# SolarTracker.net
KiCad netlist of a schematic drawn in EAGLE
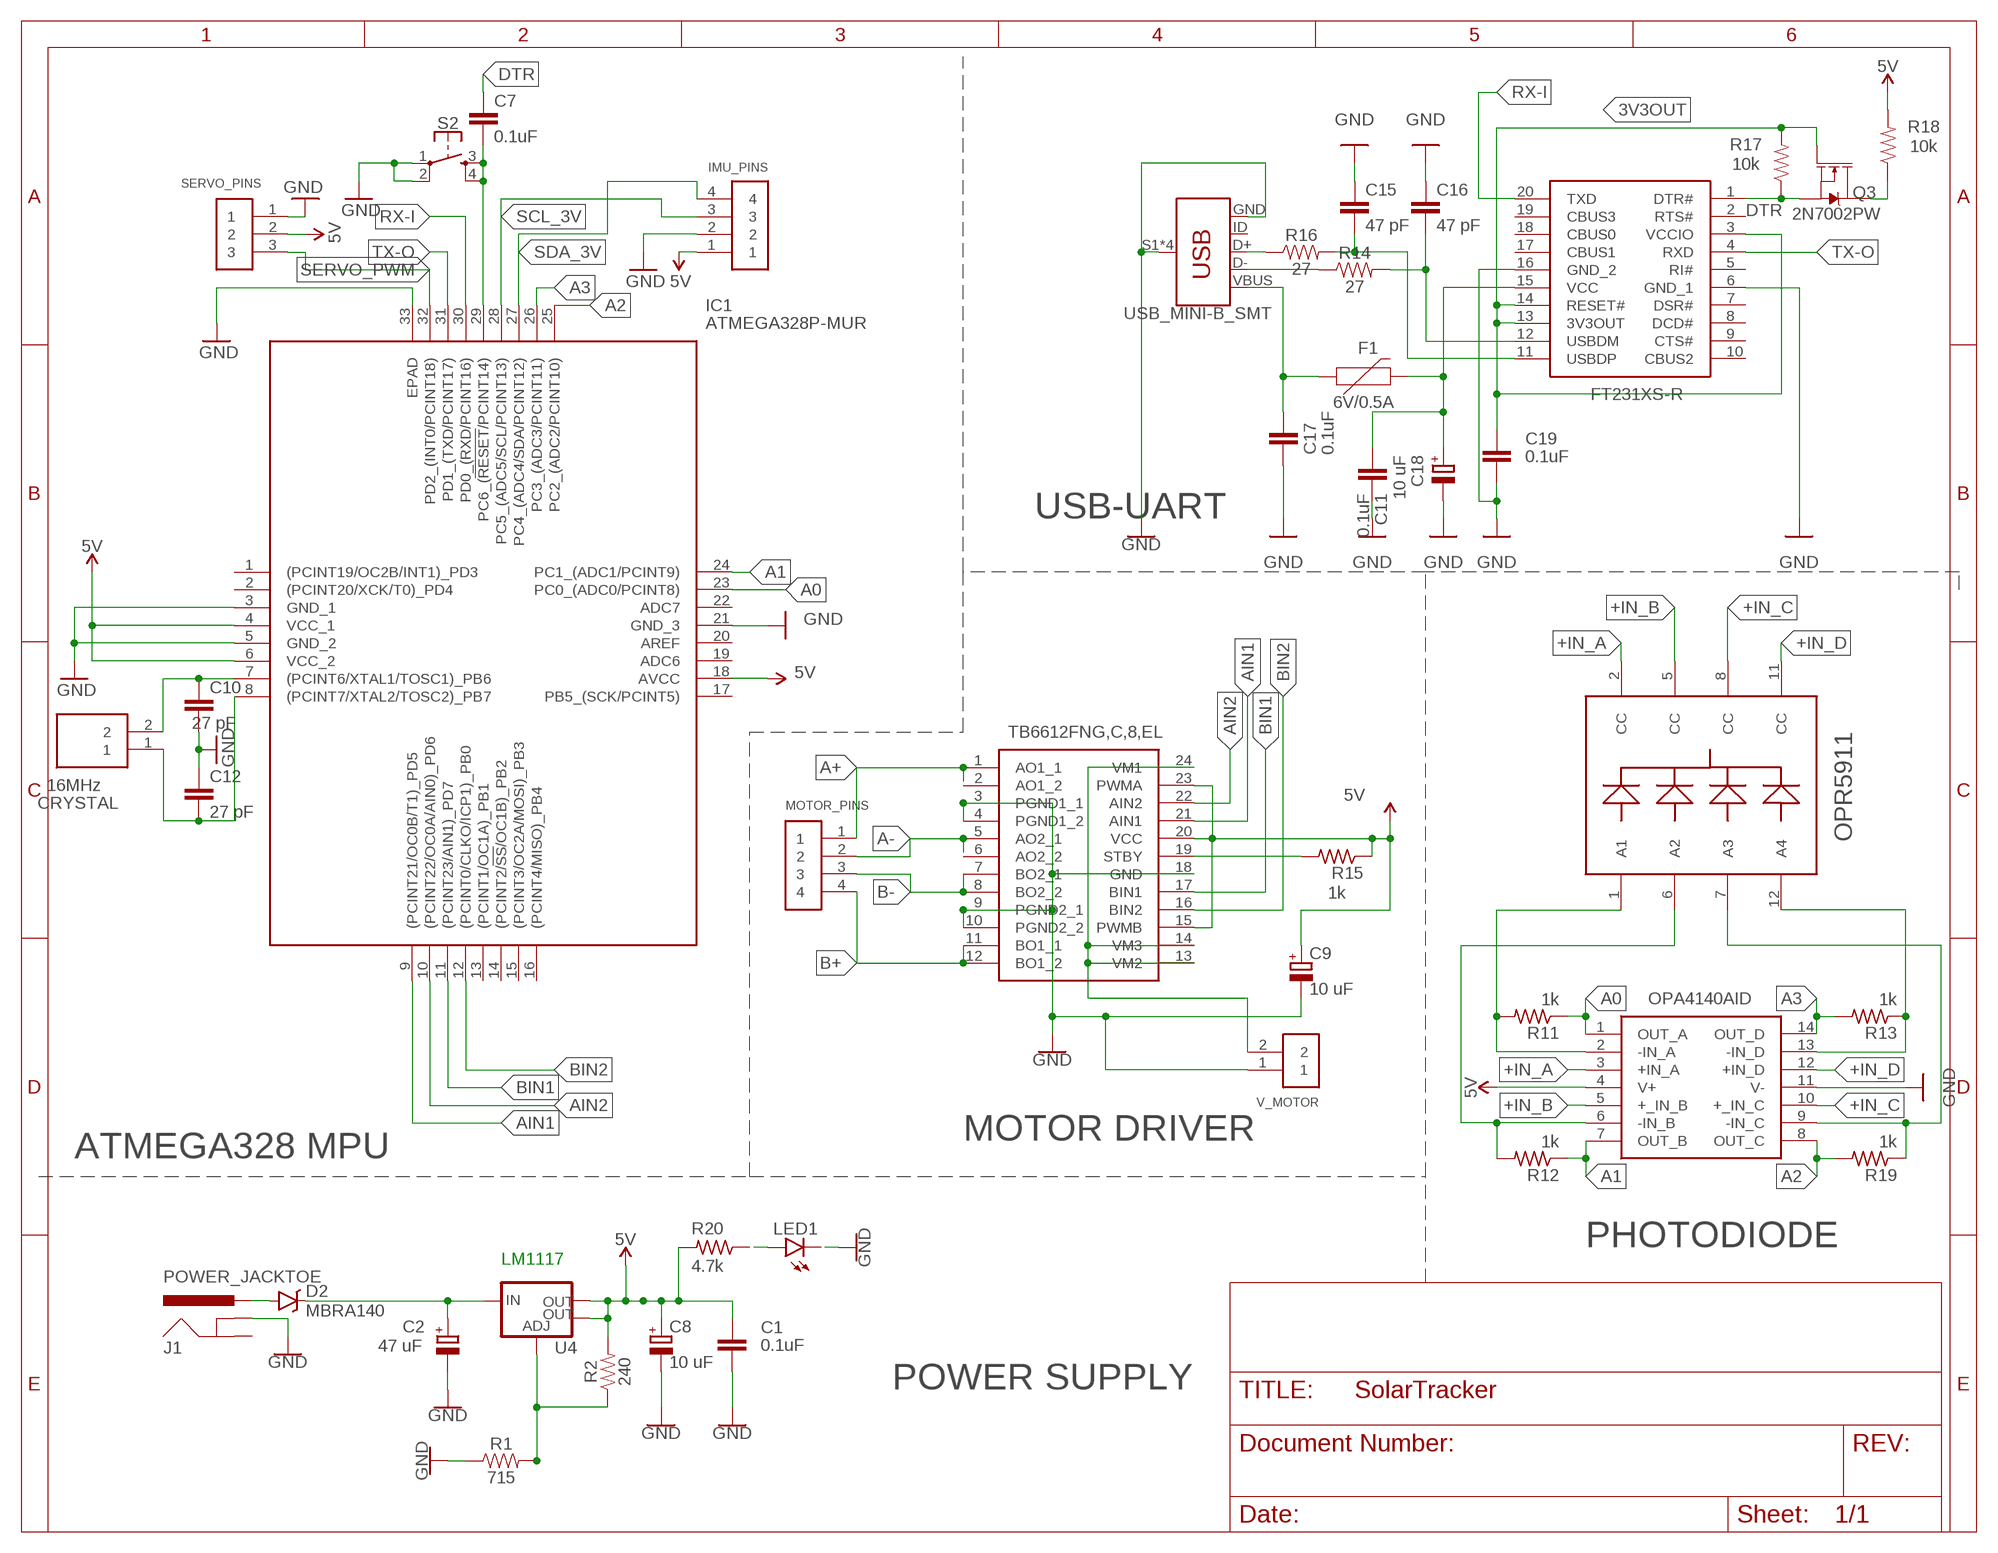
[diagram p0: schematic, sheet 1]

(export (version "E")
  (design (tool "Eeschema 10.0.6"))
  (components
    (comp (ref "C1")
      (value "0.1uF")
      (footprint "eagle-import:C0603")
      (libsource (lib "eagle-import") (part "C-EUC0603"))
    )
    (comp (ref "C2")
      (value "47 uF")
      (footprint "eagle-import:E2,5-6")
      (libsource (lib "eagle-import") (part "CPOL-EUE2.5-6"))
    )
    (comp (ref "C7")
      (value "0.1uF")
      (footprint "eagle-import:C0603")
      (libsource (lib "eagle-import") (part "C-EUC0603"))
    )
    (comp (ref "C8")
      (value "10 uF")
      (footprint "eagle-import:E2,5-6")
      (libsource (lib "eagle-import") (part "CPOL-EUE2.5-6"))
    )
    (comp (ref "C9")
      (value "10 uF")
      (footprint "eagle-import:E2,5-6")
      (libsource (lib "eagle-import") (part "CPOL-EUE2.5-6"))
    )
    (comp (ref "C10")
      (value "27 pF")
      (footprint "eagle-import:C025-025X050")
      (libsource (lib "eagle-import") (part "C-EU025-025X050"))
    )
    (comp (ref "C11")
      (value "0.1uF")
      (footprint "eagle-import:C0603")
      (libsource (lib "eagle-import") (part "C-EUC0603"))
    )
    (comp (ref "C12")
      (value "27 pF")
      (footprint "eagle-import:C025-025X050")
      (libsource (lib "eagle-import") (part "C-EU025-025X050"))
    )
    (comp (ref "C15")
      (value "47 pF")
      (footprint "eagle-import:C0805")
      (libsource (lib "eagle-import") (part "C-EUC0805"))
    )
    (comp (ref "C16")
      (value "47 pF")
      (footprint "eagle-import:C0805")
      (libsource (lib "eagle-import") (part "C-EUC0805"))
    )
    (comp (ref "C17")
      (value "0.1uF")
      (footprint "eagle-import:C0603")
      (libsource (lib "eagle-import") (part "C-EUC0603"))
    )
    (comp (ref "C18")
      (value "10 uF")
      (footprint "eagle-import:E2,5-6")
      (libsource (lib "eagle-import") (part "CPOL-EUE2.5-6"))
    )
    (comp (ref "C19")
      (value "0.1uF")
      (footprint "eagle-import:C0603")
      (libsource (lib "eagle-import") (part "C-EUC0603"))
    )
    (comp (ref "CRYSTAL")
      (value "16MHz")
      (footprint "eagle-import:HC49")
      (fields
        (field (name "MANUFACTURER_PART_NUMBER") "HC-49/U-S16000000ABJB")
        (field (name "MOUSER_PART_NUMBER") "695-HC49US16.0ABJB")
      )
      (libsource (lib "eagle-import") (part "HC-49_U-S16000000ABJB"))
    )
    (comp (ref "D2")
      (value "MBRA140")
      (footprint "eagle-import:SMA-DIODE")
      (fields (field (name "MF") "ON Semiconductor"))
      (libsource (lib "eagle-import") (part "MBRA140"))
    )
    (comp (ref "F1")
      (value "6V/0.5A")
      (footprint "eagle-import:1206")
      (libsource (lib "eagle-import") (part "PTC-HALF_AMP"))
    )
    (comp (ref "IC1")
      (value "ATMEGA328P-MUR")
      (footprint "eagle-import:QFN50P500X500X100-33N")
      (fields (field (name "MOUSER_PART_NUMBER") "556-ATMEGA328P-MUR"))
      (libsource (lib "eagle-import") (part "ATMEGA328P-MUR"))
    )
    (comp (ref "IC2")
      (value "FT231XS-R")
      (footprint "eagle-import:SOP64P599X175-20N")
      (libsource (lib "eagle-import") (part "FT231XS-R"))
    )
    (comp (ref "IC3")
      (value "OPA4140AID")
      (footprint "eagle-import:SOIC127P600X175-14N")
      (fields (field (name "MOUSER_PART_NUMBER") "595-OPA4140AID"))
      (libsource (lib "eagle-import") (part "OPA4140AID"))
    )
    (comp (ref "J1")
      (value "POWER_JACKTOE")
      (footprint "eagle-import:POWER_JACK_SMD_OVERPASTE_TOE")
      (libsource (lib "eagle-import") (part "POWER_JACKTOE"))
    )
    (comp (ref "J2")
      (value "USB_MINI-B_SMT")
      (footprint "eagle-import:USB-MINIB")
      (libsource (lib "eagle-import") (part "USB_MINI-B_SMT"))
    )
    (comp (ref "J4")
      (value "IMU_PINS")
      (footprint "eagle-import:61300411121")
      (fields
        (field (name "DIGI_KEY_PART_NUMBER") "732-5317-ND")
        (field (name "MANUFACTURER") "Wurth Electronics Inc.")
        (field (name "MPN") "61300411121")
        (field (name "CREATED_BY") "PCBLayout.com")
      )
      (libsource (lib "eagle-import") (part "61300411121"))
    )
    (comp (ref "LED1")
      (value "LED5MM")
      (footprint "eagle-import:LED5MM")
      (libsource (lib "eagle-import") (part "LED5MM"))
    )
    (comp (ref "MOTOR_DRIVER")
      (value "TB6612FNG,C,8,EL")
      (footprint "eagle-import:SOP65P760X160-24N")
      (fields (field (name "MOUSER_PART_NUMBER") "757-TB6612FNGC8EL"))
      (libsource (lib "eagle-import") (part "TB6612FNG,C,8,EL"))
    )
    (comp (ref "MOTOR_PINS")
      (value "61300411121")
      (footprint "eagle-import:61300411121")
      (fields
        (field (name "DIGI_KEY_PART_NUMBER") "732-5317-ND")
        (field (name "MANUFACTURER") "Wurth Electronics Inc.")
        (field (name "CREATED_BY") "PCBLayout.com")
      )
      (libsource (lib "eagle-import") (part "61300411121"))
    )
    (comp (ref "OPR5911")
      (value "OPR5911")
      (footprint "eagle-import:OPR5911-12")
      (libsource (lib "eagle-import") (part "OPR5911"))
    )
    (comp (ref "Q3")
      (value "2N7002PW")
      (footprint "eagle-import:SOT323")
      (libsource (lib "eagle-import") (part "MOSFET-NCH-2N7002PW"))
    )
    (comp (ref "R1")
      (value "715")
      (footprint "eagle-import:0603")
      (libsource (lib "eagle-import") (part "715OHM-0603-1/10W-1%"))
    )
    (comp (ref "R2")
      (value "240")
      (footprint "eagle-import:0603")
      (libsource (lib "eagle-import") (part "240OHM-0603-1/10W-1%"))
    )
    (comp (ref "R11")
      (value "1k")
      (footprint "eagle-import:0207_10")
      (libsource (lib "eagle-import") (part "R-US_0207/10"))
    )
    (comp (ref "R12")
      (value "1k")
      (footprint "eagle-import:0207_10")
      (libsource (lib "eagle-import") (part "R-US_0207/10"))
    )
    (comp (ref "R13")
      (value "1k")
      (footprint "eagle-import:0207_10")
      (libsource (lib "eagle-import") (part "R-US_0207/10"))
    )
    (comp (ref "R14")
      (value "27")
      (footprint "eagle-import:0603")
      (libsource (lib "eagle-import") (part "4.7KOHM-0603-1/10W-1%"))
    )
    (comp (ref "R15")
      (value "1k")
      (footprint "eagle-import:0207_10")
      (libsource (lib "eagle-import") (part "R-US_0207/10"))
    )
    (comp (ref "R16")
      (value "27")
      (footprint "eagle-import:0603")
      (libsource (lib "eagle-import") (part "4.7KOHM-0603-1/10W-1%"))
    )
    (comp (ref "R17")
      (value "10k")
      (footprint "eagle-import:0603")
      (libsource (lib "eagle-import") (part "4.7KOHM-0603-1/10W-1%"))
    )
    (comp (ref "R18")
      (value "10k")
      (footprint "eagle-import:0603")
      (libsource (lib "eagle-import") (part "4.7KOHM-0603-1/10W-1%"))
    )
    (comp (ref "R19")
      (value "1k")
      (footprint "eagle-import:0207_10")
      (libsource (lib "eagle-import") (part "R-US_0207/10"))
    )
    (comp (ref "R20")
      (value "4.7k")
      (footprint "eagle-import:0207_10")
      (libsource (lib "eagle-import") (part "R-US_0207/10"))
    )
    (comp (ref "S2")
      (value "MOMENTARY-SWITCH-SPST-2-SMD-5.2MM")
      (footprint "eagle-import:TACTILE_SWITCH_SMD_5.2MM")
      (libsource (lib "eagle-import") (part "MOMENTARY-SWITCH-SPST-2-SMD-5.2MM"))
    )
    (comp (ref "SERVO_PINS")
      (value "61300311121")
      (footprint "eagle-import:61300311121")
      (fields
        (field (name "DIGI_KEY_PART_NUMBER") "732-5316-ND")
        (field (name "MANUFACTURER") "Wurth Electronics Inc.")
        (field (name "CREATED_BY") "PCBLayout.com")
      )
      (libsource (lib "eagle-import") (part "61300311121"))
    )
    (comp (ref "U4")
      (value "V_REG_LM1117SOT223")
      (footprint "eagle-import:SOT223")
      (libsource (lib "eagle-import") (part "V_REG_LM1117SOT223"))
    )
    (comp (ref "V_MOTOR")
      (value "61300211121")
      (footprint "eagle-import:61300211121")
      (fields
        (field (name "DIGI_KEY_PART_NUMBER") "732-5315-ND")
        (field (name "MANUFACTURER") "Wurth Electronics Inc.")
        (field (name "CREATED_BY") "PCBLayout.com")
      )
      (libsource (lib "eagle-import") (part "61300211121"))
    )
  )
  (nets
    (net (code "1") (name "+IN_A") (class "Default")
      (node (ref "IC3") (pin "3") (pinfunction "+IN_A_3") (pintype "bidirectional"))
      (node (ref "OPR5911") (pin "2") (pinfunction "CC_2") (pintype "bidirectional"))
    )
    (net (code "2") (name "+IN_B") (class "Default")
      (node (ref "IC3") (pin "5") (pinfunction "+_IN_B_5") (pintype "bidirectional"))
      (node (ref "OPR5911") (pin "5") (pinfunction "CC_5") (pintype "bidirectional"))
    )
    (net (code "3") (name "+IN_C") (class "Default")
      (node (ref "IC3") (pin "10") (pinfunction "+_IN_C_10") (pintype "bidirectional"))
      (node (ref "OPR5911") (pin "8") (pinfunction "CC_8") (pintype "bidirectional"))
    )
    (net (code "4") (name "+IN_D") (class "Default")
      (node (ref "IC3") (pin "12") (pinfunction "+IN_D_12") (pintype "bidirectional"))
      (node (ref "OPR5911") (pin "11") (pinfunction "CC_11") (pintype "bidirectional"))
    )
    (net (code "5") (name "3V3OUT") (class "Default")
      (node (ref "C19") (pin "1") (pinfunction "1_1") (pintype "passive"))
      (node (ref "IC2") (pin "13") (pinfunction "3V3OUT_13") (pintype "bidirectional"))
      (node (ref "IC2") (pin "14") (pinfunction "RESET#_14") (pintype "bidirectional"))
      (node (ref "IC2") (pin "3") (pinfunction "VCCIO_3") (pintype "bidirectional"))
      (node (ref "Q3") (pin "1") (pinfunction "G_1") (pintype "bidirectional"))
      (node (ref "R17") (pin "2") (pinfunction "2_2") (pintype "passive"))
    )
    (net (code "6") (name "5V") (class "Default")
      (node (ref "C1") (pin "1") (pinfunction "1_1") (pintype "passive"))
      (node (ref "C8") (pin "+") (pinfunction "+_+") (pintype "passive"))
      (node (ref "C9") (pin "+") (pinfunction "+_+") (pintype "passive"))
      (node (ref "IC1") (pin "18") (pinfunction "AVCC_18") (pintype "bidirectional"))
      (node (ref "IC1") (pin "4") (pinfunction "VCC_1_4") (pintype "bidirectional"))
      (node (ref "IC1") (pin "6") (pinfunction "VCC_2_6") (pintype "bidirectional"))
      (node (ref "IC3") (pin "4") (pinfunction "V+_4") (pintype "bidirectional"))
      (node (ref "J4") (pin "1") (pinfunction "1_1") (pintype "passive"))
      (node (ref "MOTOR_DRIVER") (pin "15") (pinfunction "PWMB_15") (pintype "bidirectional"))
      (node (ref "MOTOR_DRIVER") (pin "20") (pinfunction "VCC_20") (pintype "bidirectional"))
      (node (ref "MOTOR_DRIVER") (pin "23") (pinfunction "PWMA_23") (pintype "bidirectional"))
      (node (ref "R15") (pin "1") (pinfunction "1_1") (pintype "passive"))
      (node (ref "R18") (pin "2") (pinfunction "2_2") (pintype "passive"))
      (node (ref "R2") (pin "2") (pinfunction "2_2") (pintype "passive"))
      (node (ref "R20") (pin "2") (pinfunction "2_2") (pintype "passive"))
      (node (ref "SERVO_PINS") (pin "2") (pinfunction "2_2") (pintype "passive"))
      (node (ref "U4") (pin "2") (pinfunction "OUT_2") (pintype "output"))
      (node (ref "U4") (pin "4") (pinfunction "OUT_4") (pintype "output"))
    )
    (net (code "7") (name "A+") (class "Default")
      (node (ref "MOTOR_DRIVER") (pin "1") (pinfunction "AO1_1_1") (pintype "bidirectional"))
      (node (ref "MOTOR_DRIVER") (pin "2") (pinfunction "AO1_2_2") (pintype "bidirectional"))
      (node (ref "MOTOR_PINS") (pin "1") (pinfunction "1_1") (pintype "passive"))
    )
    (net (code "8") (name "A-") (class "Default")
      (node (ref "MOTOR_DRIVER") (pin "5") (pinfunction "AO2_1_5") (pintype "bidirectional"))
      (node (ref "MOTOR_DRIVER") (pin "6") (pinfunction "AO2_2_6") (pintype "bidirectional"))
      (node (ref "MOTOR_PINS") (pin "2") (pinfunction "2_2") (pintype "passive"))
    )
    (net (code "9") (name "A0") (class "Default")
      (node (ref "IC1") (pin "23") (pinfunction "PC0_(ADC0/PCINT8)_23") (pintype "bidirectional"))
      (node (ref "IC3") (pin "1") (pinfunction "OUT_A_1") (pintype "bidirectional"))
      (node (ref "R11") (pin "1") (pinfunction "1_1") (pintype "passive"))
    )
    (net (code "10") (name "A1") (class "Default")
      (node (ref "IC1") (pin "24") (pinfunction "PC1_(ADC1/PCINT9)_24") (pintype "bidirectional"))
      (node (ref "IC3") (pin "7") (pinfunction "OUT_B_7") (pintype "bidirectional"))
      (node (ref "R12") (pin "1") (pinfunction "1_1") (pintype "passive"))
    )
    (net (code "11") (name "A2") (class "Default")
      (node (ref "IC1") (pin "25") (pinfunction "PC2_(ADC2/PCINT10)_25") (pintype "bidirectional"))
      (node (ref "IC3") (pin "8") (pinfunction "OUT_C_8") (pintype "bidirectional"))
      (node (ref "R19") (pin "2") (pinfunction "2_2") (pintype "passive"))
    )
    (net (code "12") (name "A3") (class "Default")
      (node (ref "IC1") (pin "26") (pinfunction "PC3_(ADC3/PCINT11)_26") (pintype "bidirectional"))
      (node (ref "IC3") (pin "14") (pinfunction "OUT_D_14") (pintype "bidirectional"))
      (node (ref "R13") (pin "2") (pinfunction "2_2") (pintype "passive"))
    )
    (net (code "13") (name "AIN1") (class "Default")
      (node (ref "IC1") (pin "9") (pinfunction "(PCINT21/OC0B/T1)_PD5_9") (pintype "bidirectional"))
      (node (ref "MOTOR_DRIVER") (pin "21") (pinfunction "AIN1_21") (pintype "bidirectional"))
    )
    (net (code "14") (name "AIN2") (class "Default")
      (node (ref "IC1") (pin "10") (pinfunction "(PCINT22/OC0A/AIN0)_PD6_10") (pintype "bidirectional"))
      (node (ref "MOTOR_DRIVER") (pin "22") (pinfunction "AIN2_22") (pintype "bidirectional"))
    )
    (net (code "15") (name "B+") (class "Default")
      (node (ref "MOTOR_DRIVER") (pin "11") (pinfunction "BO1_1_11") (pintype "bidirectional"))
      (node (ref "MOTOR_DRIVER") (pin "12") (pinfunction "BO1_2_12") (pintype "bidirectional"))
      (node (ref "MOTOR_PINS") (pin "4") (pinfunction "4_4") (pintype "passive"))
    )
    (net (code "16") (name "B-") (class "Default")
      (node (ref "MOTOR_DRIVER") (pin "7") (pinfunction "BO2_1_7") (pintype "bidirectional"))
      (node (ref "MOTOR_DRIVER") (pin "8") (pinfunction "BO2_2_8") (pintype "bidirectional"))
      (node (ref "MOTOR_PINS") (pin "3") (pinfunction "3_3") (pintype "passive"))
    )
    (net (code "17") (name "BIN1") (class "Default")
      (node (ref "IC1") (pin "11") (pinfunction "(PCINT23/AIN1)_PD7_11") (pintype "bidirectional"))
      (node (ref "MOTOR_DRIVER") (pin "17") (pinfunction "BIN1_17") (pintype "bidirectional"))
    )
    (net (code "18") (name "BIN2") (class "Default")
      (node (ref "IC1") (pin "12") (pinfunction "(PCINT0/CLKO/ICP1)_PB0_12") (pintype "bidirectional"))
      (node (ref "MOTOR_DRIVER") (pin "16") (pinfunction "BIN2_16") (pintype "bidirectional"))
    )
    (net (code "19") (name "DTR") (class "Default")
      (node (ref "C7") (pin "1") (pinfunction "1_1") (pintype "passive"))
      (node (ref "IC2") (pin "1") (pinfunction "DTR#_1") (pintype "bidirectional"))
      (node (ref "Q3") (pin "2") (pinfunction "S_2") (pintype "bidirectional"))
      (node (ref "R17") (pin "1") (pinfunction "1_1") (pintype "passive"))
    )
    (net (code "20") (name "GND") (class "Default")
      (node (ref "C1") (pin "2") (pinfunction "2_2") (pintype "passive"))
      (node (ref "C10") (pin "2") (pinfunction "2_2") (pintype "passive"))
      (node (ref "C11") (pin "1") (pinfunction "1_1") (pintype "passive"))
      (node (ref "C12") (pin "1") (pinfunction "1_1") (pintype "passive"))
      (node (ref "C15") (pin "1") (pinfunction "1_1") (pintype "passive"))
      (node (ref "C16") (pin "1") (pinfunction "1_1") (pintype "passive"))
      (node (ref "C17") (pin "2") (pinfunction "2_2") (pintype "passive"))
      (node (ref "C18") (pin "-") (pinfunction "-_-") (pintype "passive"))
      (node (ref "C19") (pin "2") (pinfunction "2_2") (pintype "passive"))
      (node (ref "C2") (pin "-") (pinfunction "-_-") (pintype "passive"))
      (node (ref "C8") (pin "-") (pinfunction "-_-") (pintype "passive"))
      (node (ref "C9") (pin "-") (pinfunction "-_-") (pintype "passive"))
      (node (ref "IC1") (pin "21") (pinfunction "GND_3_21") (pintype "bidirectional"))
      (node (ref "IC1") (pin "3") (pinfunction "GND_1_3") (pintype "bidirectional"))
      (node (ref "IC1") (pin "33") (pinfunction "EPAD_33") (pintype "bidirectional"))
      (node (ref "IC1") (pin "5") (pinfunction "GND_2_5") (pintype "bidirectional"))
      (node (ref "IC2") (pin "16") (pinfunction "GND_2_16") (pintype "bidirectional"))
      (node (ref "IC2") (pin "6") (pinfunction "GND_1_6") (pintype "bidirectional"))
      (node (ref "IC3") (pin "11") (pinfunction "V-_11") (pintype "bidirectional"))
      (node (ref "J1") (pin "GND") (pinfunction "GNDBREAK_GND") (pintype "bidirectional"))
      (node (ref "J2") (pin "GND") (pinfunction "GND_GND") (pintype "power_in"))
      (node (ref "J2") (pin "S1") (pinfunction "SHIELD_S1") (pintype "bidirectional"))
      (node (ref "J2") (pin "S2") (pinfunction "SHIELD_S2") (pintype "bidirectional"))
      (node (ref "J2") (pin "S3") (pinfunction "SHIELD_S3") (pintype "bidirectional"))
      (node (ref "J2") (pin "S4") (pinfunction "SHIELD_S4") (pintype "bidirectional"))
      (node (ref "J4") (pin "2") (pinfunction "2_2") (pintype "passive"))
      (node (ref "LED1") (pin "K") (pinfunction "C_K") (pintype "passive"))
      (node (ref "MOTOR_DRIVER") (pin "10") (pinfunction "PGND2_2_10") (pintype "bidirectional"))
      (node (ref "MOTOR_DRIVER") (pin "18") (pinfunction "GND_18") (pintype "bidirectional"))
      (node (ref "MOTOR_DRIVER") (pin "3") (pinfunction "PGND1_1_3") (pintype "bidirectional"))
      (node (ref "MOTOR_DRIVER") (pin "4") (pinfunction "PGND1_2_4") (pintype "bidirectional"))
      (node (ref "MOTOR_DRIVER") (pin "9") (pinfunction "PGND2_1_9") (pintype "bidirectional"))
      (node (ref "R1") (pin "1") (pinfunction "1_1") (pintype "passive"))
      (node (ref "S2") (pin "1") (pinfunction "1_1") (pintype "passive"))
      (node (ref "S2") (pin "2") (pinfunction "2_2") (pintype "passive"))
      (node (ref "SERVO_PINS") (pin "1") (pinfunction "1_1") (pintype "passive"))
      (node (ref "V_MOTOR") (pin "1") (pinfunction "1_1") (pintype "passive"))
    )
    (net (code "21") (name "Net-(C17-Pad1)") (class "Default")
      (node (ref "C17") (pin "1") (pinfunction "1_1") (pintype "passive"))
      (node (ref "F1") (pin "1") (pinfunction "1_1") (pintype "bidirectional"))
      (node (ref "J2") (pin "VBUS") (pinfunction "VBUS_VBUS") (pintype "power_in"))
    )
    (net (code "22") (name "Net-(IC1-(PCINT6{slash}XTAL1{slash}TOSC1)_PB6)") (class "Default")
      (node (ref "C10") (pin "1") (pinfunction "1_1") (pintype "passive"))
      (node (ref "CRYSTAL") (pin "2") (pinfunction "2_2") (pintype "bidirectional"))
      (node (ref "IC1") (pin "7") (pinfunction "(PCINT6/XTAL1/TOSC1)_PB6_7") (pintype "bidirectional"))
    )
    (net (code "23") (name "Net-(IC1-(PCINT7{slash}XTAL2{slash}TOSC2)_PB7)") (class "Default")
      (node (ref "C12") (pin "2") (pinfunction "2_2") (pintype "passive"))
      (node (ref "CRYSTAL") (pin "1") (pinfunction "1_1") (pintype "bidirectional"))
      (node (ref "IC1") (pin "8") (pinfunction "(PCINT7/XTAL2/TOSC2)_PB7_8") (pintype "bidirectional"))
    )
    (net (code "24") (name "Net-(IC1-PC6_(~{RESET}{slash}PCINT14))") (class "Default")
      (node (ref "C7") (pin "2") (pinfunction "2_2") (pintype "passive"))
      (node (ref "IC1") (pin "29") (pinfunction "PC6_(~{RESET}/PCINT14)_29") (pintype "bidirectional"))
      (node (ref "S2") (pin "3") (pinfunction "3_3") (pintype "passive"))
      (node (ref "S2") (pin "4") (pinfunction "4_4") (pintype "passive"))
    )
    (net (code "25") (name "Net-(IC2-USBDM)") (class "Default")
      (node (ref "C16") (pin "2") (pinfunction "2_2") (pintype "passive"))
      (node (ref "IC2") (pin "12") (pinfunction "USBDM_12") (pintype "bidirectional"))
      (node (ref "R14") (pin "2") (pinfunction "2_2") (pintype "passive"))
    )
    (net (code "26") (name "Net-(IC2-USBDP)") (class "Default")
      (node (ref "C15") (pin "2") (pinfunction "2_2") (pintype "passive"))
      (node (ref "IC2") (pin "11") (pinfunction "USBDP_11") (pintype "bidirectional"))
      (node (ref "R16") (pin "2") (pinfunction "2_2") (pintype "passive"))
    )
    (net (code "27") (name "Net-(IC2-VCC)") (class "Default")
      (node (ref "C11") (pin "2") (pinfunction "2_2") (pintype "passive"))
      (node (ref "C18") (pin "+") (pinfunction "+_+") (pintype "passive"))
      (node (ref "F1") (pin "2") (pinfunction "2_2") (pintype "bidirectional"))
      (node (ref "IC2") (pin "15") (pinfunction "VCC_15") (pintype "bidirectional"))
    )
    (net (code "28") (name "Net-(IC3--IN_A)") (class "Default")
      (node (ref "IC3") (pin "2") (pinfunction "-IN_A_2") (pintype "bidirectional"))
      (node (ref "OPR5911") (pin "1") (pinfunction "A1_1") (pintype "bidirectional"))
      (node (ref "R11") (pin "2") (pinfunction "2_2") (pintype "passive"))
    )
    (net (code "29") (name "Net-(IC3--IN_B)") (class "Default")
      (node (ref "IC3") (pin "6") (pinfunction "-IN_B_6") (pintype "bidirectional"))
      (node (ref "OPR5911") (pin "6") (pinfunction "A2_6") (pintype "bidirectional"))
      (node (ref "R12") (pin "2") (pinfunction "2_2") (pintype "passive"))
    )
    (net (code "30") (name "Net-(IC3--IN_C)") (class "Default")
      (node (ref "IC3") (pin "9") (pinfunction "-IN_C_9") (pintype "bidirectional"))
      (node (ref "OPR5911") (pin "7") (pinfunction "A3_7") (pintype "bidirectional"))
      (node (ref "R19") (pin "1") (pinfunction "1_1") (pintype "passive"))
    )
    (net (code "31") (name "Net-(IC3--IN_D)") (class "Default")
      (node (ref "IC3") (pin "13") (pinfunction "-IN_D_13") (pintype "bidirectional"))
      (node (ref "OPR5911") (pin "12") (pinfunction "A4_12") (pintype "bidirectional"))
      (node (ref "R13") (pin "1") (pinfunction "1_1") (pintype "passive"))
    )
    (net (code "32") (name "Net-(J1-PWR)") (class "Default")
      (node (ref "D2") (pin "A") (pinfunction "A_A") (pintype "passive"))
      (node (ref "J1") (pin "VIN0") (pinfunction "PWR_VIN0") (pintype "bidirectional"))
    )
    (net (code "33") (name "Net-(J2-PadD+)") (class "Default")
      (node (ref "J2") (pin "D+") (pinfunction "D+_D+") (pintype "bidirectional"))
      (node (ref "R16") (pin "1") (pinfunction "1_1") (pintype "passive"))
    )
    (net (code "34") (name "Net-(J2-PadD-)") (class "Default")
      (node (ref "J2") (pin "D-") (pinfunction "D-_D-") (pintype "bidirectional"))
      (node (ref "R14") (pin "1") (pinfunction "1_1") (pintype "passive"))
    )
    (net (code "35") (name "Net-(LED1-PadA)") (class "Default")
      (node (ref "LED1") (pin "A") (pinfunction "A_A") (pintype "passive"))
      (node (ref "R20") (pin "1") (pinfunction "1_1") (pintype "passive"))
    )
    (net (code "36") (name "Net-(MOTOR_DRIVER-STBY)") (class "Default")
      (node (ref "MOTOR_DRIVER") (pin "19") (pinfunction "STBY_19") (pintype "bidirectional"))
      (node (ref "R15") (pin "2") (pinfunction "2_2") (pintype "passive"))
    )
    (net (code "37") (name "Net-(MOTOR_DRIVER-VM1)") (class "Default")
      (node (ref "MOTOR_DRIVER") (pin "13") (pinfunction "VM2_13") (pintype "bidirectional"))
      (node (ref "MOTOR_DRIVER") (pin "14") (pinfunction "VM3_14") (pintype "bidirectional"))
      (node (ref "MOTOR_DRIVER") (pin "24") (pinfunction "VM1_24") (pintype "bidirectional"))
      (node (ref "V_MOTOR") (pin "2") (pinfunction "2_2") (pintype "passive"))
    )
    (net (code "38") (name "Net-(Q3-D)") (class "Default")
      (node (ref "Q3") (pin "3") (pinfunction "D_3") (pintype "bidirectional"))
      (node (ref "R18") (pin "1") (pinfunction "1_1") (pintype "passive"))
    )
    (net (code "39") (name "Net-(U4-ADJ)") (class "Default")
      (node (ref "R1") (pin "2") (pinfunction "2_2") (pintype "passive"))
      (node (ref "R2") (pin "1") (pinfunction "1_1") (pintype "passive"))
      (node (ref "U4") (pin "1") (pinfunction "ADJ_1") (pintype "input"))
    )
    (net (code "40") (name "Net-(U4-IN)") (class "Default")
      (node (ref "C2") (pin "+") (pinfunction "+_+") (pintype "passive"))
      (node (ref "D2") (pin "C") (pinfunction "C_C") (pintype "passive"))
      (node (ref "U4") (pin "3") (pinfunction "IN_3") (pintype "input"))
    )
    (net (code "41") (name "RX-I") (class "Default")
      (node (ref "IC1") (pin "30") (pinfunction "PD0_(RXD/PCINT16)_30") (pintype "bidirectional"))
      (node (ref "IC2") (pin "20") (pinfunction "TXD_20") (pintype "bidirectional"))
    )
    (net (code "42") (name "SCL_3V") (class "Default")
      (node (ref "IC1") (pin "28") (pinfunction "PC5_(ADC5/SCL/PCINT13)_28") (pintype "bidirectional"))
      (node (ref "J4") (pin "3") (pinfunction "3_3") (pintype "passive"))
    )
    (net (code "43") (name "SDA_3V") (class "Default")
      (node (ref "IC1") (pin "27") (pinfunction "PC4_(ADC4/SDA/PCINT12)_27") (pintype "bidirectional"))
      (node (ref "J4") (pin "4") (pinfunction "4_4") (pintype "passive"))
    )
    (net (code "44") (name "SERVO_PWM") (class "Default")
      (node (ref "IC1") (pin "32") (pinfunction "PD2_(INT0/PCINT18)_32") (pintype "bidirectional"))
      (node (ref "SERVO_PINS") (pin "3") (pinfunction "3_3") (pintype "passive"))
    )
    (net (code "45") (name "TX-O") (class "Default")
      (node (ref "IC1") (pin "31") (pinfunction "PD1_(TXD/PCINT17)_31") (pintype "bidirectional"))
      (node (ref "IC2") (pin "4") (pinfunction "RXD_4") (pintype "bidirectional"))
    )
    (net (code "46") (name "unconnected-(IC1-(PCINT1{slash}OC1A)_PB1-Pad13)") (class "Default")
      (node (ref "IC1") (pin "13") (pinfunction "(PCINT1/OC1A)_PB1_13") (pintype "bidirectional"))
    )
    (net (code "47") (name "unconnected-(IC1-(PCINT2{slash}~{SS}{slash}OC1B)_PB2-Pad14)") (class "Default")
      (node (ref "IC1") (pin "14") (pinfunction "(PCINT2/~{SS}/OC1B)_PB2_14") (pintype "bidirectional"))
    )
    (net (code "48") (name "unconnected-(IC1-(PCINT3{slash}OC2A{slash}MOSI)_PB3-Pad15)") (class "Default")
      (node (ref "IC1") (pin "15") (pinfunction "(PCINT3/OC2A/MOSI)_PB3_15") (pintype "bidirectional"))
    )
    (net (code "49") (name "unconnected-(IC1-(PCINT4{slash}MISO)_PB4-Pad16)") (class "Default")
      (node (ref "IC1") (pin "16") (pinfunction "(PCINT4/MISO)_PB4_16") (pintype "bidirectional"))
    )
    (net (code "50") (name "unconnected-(IC1-(PCINT19{slash}OC2B{slash}INT1)_PD3-Pad1)") (class "Default")
      (node (ref "IC1") (pin "1") (pinfunction "(PCINT19/OC2B/INT1)_PD3_1") (pintype "bidirectional"))
    )
    (net (code "51") (name "unconnected-(IC1-(PCINT20{slash}XCK{slash}T0)_PD4-Pad2)") (class "Default")
      (node (ref "IC1") (pin "2") (pinfunction "(PCINT20/XCK/T0)_PD4_2") (pintype "bidirectional"))
    )
    (net (code "52") (name "unconnected-(IC1-ADC6-Pad19)") (class "Default")
      (node (ref "IC1") (pin "19") (pinfunction "ADC6_19") (pintype "bidirectional"))
    )
    (net (code "53") (name "unconnected-(IC1-ADC7-Pad22)") (class "Default")
      (node (ref "IC1") (pin "22") (pinfunction "ADC7_22") (pintype "bidirectional"))
    )
    (net (code "54") (name "unconnected-(IC1-AREF-Pad20)") (class "Default")
      (node (ref "IC1") (pin "20") (pinfunction "AREF_20") (pintype "bidirectional"))
    )
    (net (code "55") (name "unconnected-(IC1-PB5_(SCK{slash}PCINT5)-Pad17)") (class "Default")
      (node (ref "IC1") (pin "17") (pinfunction "PB5_(SCK/PCINT5)_17") (pintype "bidirectional"))
    )
    (net (code "56") (name "unconnected-(IC2-CBUS0-Pad18)") (class "Default")
      (node (ref "IC2") (pin "18") (pinfunction "CBUS0_18") (pintype "bidirectional"))
    )
    (net (code "57") (name "unconnected-(IC2-CBUS1-Pad17)") (class "Default")
      (node (ref "IC2") (pin "17") (pinfunction "CBUS1_17") (pintype "bidirectional"))
    )
    (net (code "58") (name "unconnected-(IC2-CBUS2-Pad10)") (class "Default")
      (node (ref "IC2") (pin "10") (pinfunction "CBUS2_10") (pintype "bidirectional"))
    )
    (net (code "59") (name "unconnected-(IC2-CBUS3-Pad19)") (class "Default")
      (node (ref "IC2") (pin "19") (pinfunction "CBUS3_19") (pintype "bidirectional"))
    )
    (net (code "60") (name "unconnected-(IC2-CTS#-Pad9)") (class "Default")
      (node (ref "IC2") (pin "9") (pinfunction "CTS#_9") (pintype "bidirectional"))
    )
    (net (code "61") (name "unconnected-(IC2-DCD#-Pad8)") (class "Default")
      (node (ref "IC2") (pin "8") (pinfunction "DCD#_8") (pintype "bidirectional"))
    )
    (net (code "62") (name "unconnected-(IC2-DSR#-Pad7)") (class "Default")
      (node (ref "IC2") (pin "7") (pinfunction "DSR#_7") (pintype "bidirectional"))
    )
    (net (code "63") (name "unconnected-(IC2-RI#-Pad5)") (class "Default")
      (node (ref "IC2") (pin "5") (pinfunction "RI#_5") (pintype "bidirectional"))
    )
    (net (code "64") (name "unconnected-(IC2-RTS#-Pad2)") (class "Default")
      (node (ref "IC2") (pin "2") (pinfunction "RTS#_2") (pintype "bidirectional"))
    )
    (net (code "65") (name "unconnected-(J1-GND-PadP$4)") (class "Default")
      (node (ref "J1") (pin "P$4") (pinfunction "GND_P$4") (pintype "bidirectional"))
    )
    (net (code "66") (name "unconnected-(J2-PadID)") (class "Default")
      (node (ref "J2") (pin "ID") (pinfunction "ID_ID") (pintype "bidirectional"))
    )
  )
)
